# Pulsadores.net
KiCad netlist of a schematic drawn in Altium Designer
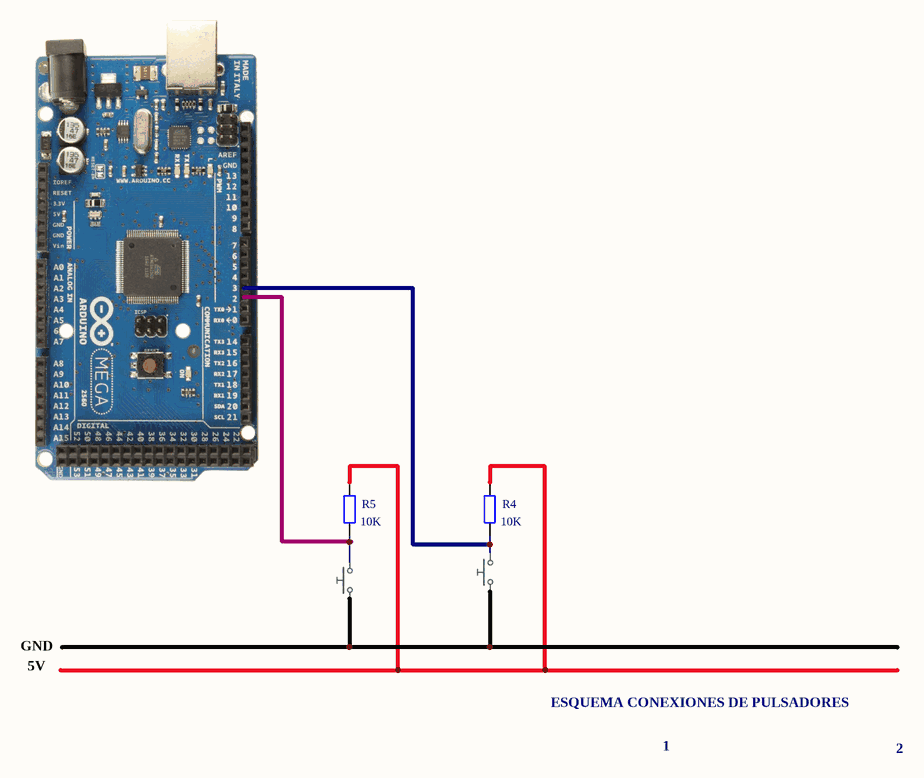
[diagram p0: Pulsadores.SchDoc]

(export (version "E")
  (design (tool "Eeschema 10.0.6"))
  (components
    (comp (ref "R4")
      (value "10K")
      (footprint "AXIAL-0.4")
      (description "Resistor")
      (fields (field (name "Comment") "Res2") (field (name "PUBLISHER") "Altium Limited"))
      (libsource (lib "Miscellaneous Devices") (part "Res2"))
    )
    (comp (ref "R5")
      (value "10K")
      (footprint "AXIAL-0.4")
      (description "Resistor")
      (fields (field (name "Comment") "Res2") (field (name "PUBLISHER") "Altium Limited"))
      (libsource (lib "Miscellaneous Devices") (part "Res2"))
    )
  )
  (nets
    (net (code "1") (name "Net-(R4-Pad2)") (class "Default")
      (node (ref "R4") (pin "2") (pinfunction "2_2") (pintype "passive"))
      (node (ref "R5") (pin "2") (pinfunction "2_2") (pintype "passive"))
    )
    (net (code "2") (name "unconnected-(R4-Pad1)") (class "Default")
      (node (ref "R4") (pin "1") (pinfunction "1_1") (pintype "passive"))
    )
    (net (code "3") (name "unconnected-(R5-Pad1)") (class "Default")
      (node (ref "R5") (pin "1") (pinfunction "1_1") (pintype "passive"))
    )
  )
)
